# MCU.net
KiCad netlist of a schematic drawn in Altium Designer
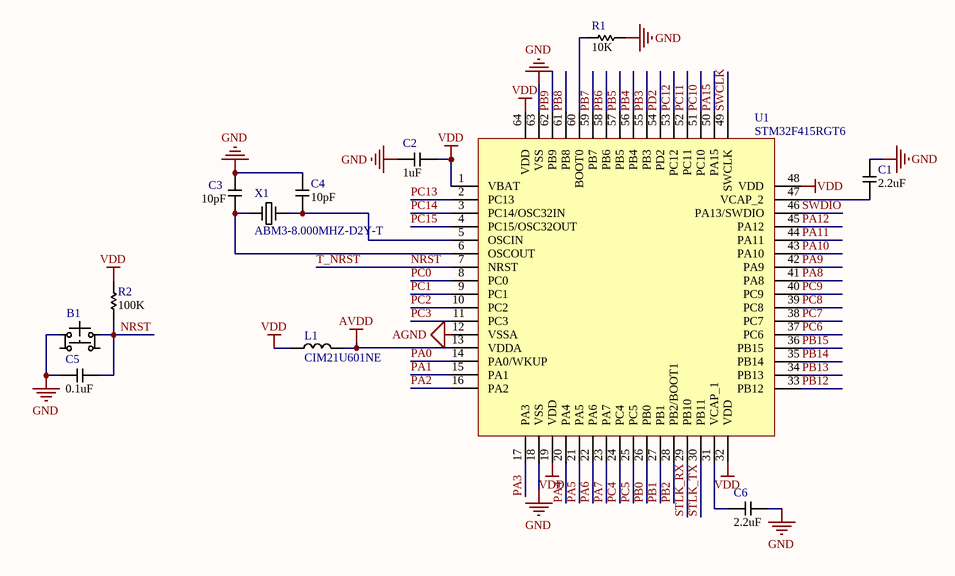
[diagram p0: MCU.SchDoc]

(export (version "E")
  (design (tool "Eeschema 10.0.6"))
  (components
    (comp (ref "B1")
      (value "DTSM-65R-V-T/R")
      (footprint "Diptronics_DTSM-65_Red_4")
      (description "Button_SMD_4_6x6x9.5_Diptronics")
      (fields (field (name "MANUFACTURER") "Diptronics"))
      (libsource (lib "Button") (part "DTSM-65R-V-T/R"))
    )
    (comp (ref "C1")
      (value "2.2uF")
      (footprint "Kemet_0805_X7R")
      (description "Cap_0805_0.1uF_25VDC_Kemet")
      (fields (field (name "MANUFACTURER") "Kemet") (field (name "VOLTAGE") "25VDC"))
      (libsource (lib "Capacitor") (part "C0805C104K3RACTU"))
    )
    (comp (ref "C2")
      (value "1uF")
      (footprint "Kemet_0805_X7R")
      (description "Cap_0805_1uF_16VDC_Kemet")
      (fields (field (name "MANUFACTURER") "Kemet") (field (name "VOLTAGE") "16VDC"))
      (libsource (lib "Capacitor") (part "C0805C105K4RACTU"))
    )
    (comp (ref "C3")
      (value "10pF")
      (footprint "Kemet_0805_X7R")
      (description "Cap_0805_0.1uF_25VDC_Kemet")
      (fields (field (name "MANUFACTURER") "Kemet") (field (name "VOLTAGE") "25VDC"))
      (libsource (lib "Capacitor") (part "C0805C104K3RACTU"))
    )
    (comp (ref "C4")
      (value "10pF")
      (footprint "Kemet_0805_X7R")
      (description "Cap_0805_0.1uF_25VDC_Kemet")
      (fields (field (name "MANUFACTURER") "Kemet") (field (name "VOLTAGE") "25VDC"))
      (libsource (lib "Capacitor") (part "C0805C104K3RACTU"))
    )
    (comp (ref "C5")
      (value "0.1uF")
      (footprint "Kemet_0805_X7R")
      (description "Cap_0805_0.1uF_25VDC_Kemet")
      (fields (field (name "MANUFACTURER") "Kemet") (field (name "VOLTAGE") "25VDC"))
      (libsource (lib "Capacitor") (part "C0805C104K3RACTU"))
    )
    (comp (ref "C6")
      (value "2.2uF")
      (footprint "Kemet_0805_X7R")
      (description "Cap_0805_0.1uF_25VDC_Kemet")
      (fields (field (name "MANUFACTURER") "Kemet") (field (name "VOLTAGE") "25VDC"))
      (libsource (lib "Capacitor") (part "C0805C104K3RACTU"))
    )
    (comp (ref "L1")
      (value "CIM21U601NE")
      (footprint "SAMSUNG_INDC200X125X110L45N")
      (description "Bead_600R_500mA_0805_Samsung")
      (fields (field (name "MANUFACTURER") "Samsung"))
      (libsource (lib "Inductor") (part "CIM21U601NE"))
    )
    (comp (ref "R1")
      (value "10K")
      (footprint "VISHAY_RESC205X125X50L35_30N")
      (description "Res_0805_0R_1/8W_Vishay")
      (fields (field (name "MANUFACTURER") "Vishay") (field (name "POWER") "1/8W"))
      (libsource (lib "Resistor") (part "CRCW08050000Z0EA"))
    )
    (comp (ref "R2")
      (value "100K")
      (footprint "VISHAY_RESC205X125X50L35_30N")
      (description "Res_0805_0R_1/8W_Vishay")
      (fields (field (name "MANUFACTURER") "Vishay") (field (name "POWER") "1/8W"))
      (libsource (lib "Resistor") (part "CRCW08050000Z0EA"))
    )
    (comp (ref "U1")
      (value "STM32F415RGT6")
      (footprint "STM_QFP64P50_1200X1200X160L60X22N")
      (description "Microcontroller_STM")
      (fields (field (name "MANUFACTURER") "STM"))
      (libsource (lib "Microcontroller") (part "STM32F415RGT6"))
    )
    (comp (ref "X1")
      (value "ABM3-8.000MHZ-D2Y-T")
      (footprint "ABRACON_XTALDFN2_500X320X130L130X200N")
      (description "Crystal_8MHz_18pF_140R_20PPM_30PPM_Abracon")
      (fields (field (name "MANUFACTURER") "Abracon"))
      (libsource (lib "Crystal") (part "ABM3-8.000MHZ-D2Y-T"))
    )
  )
  (nets
    (net (code "1") (name "/NRST") (class "Default")
      (node (ref "B1") (pin "3") (pinfunction "3_3") (pintype "passive"))
      (node (ref "C5") (pin "2") (pinfunction "2_2") (pintype "passive"))
      (node (ref "R2") (pin "2") (pinfunction "2_2") (pintype "passive"))
      (node (ref "U1") (pin "7") (pinfunction "NRST_7") (pintype "passive"))
    )
    (net (code "2") (name "/PA0") (class "Default")
      (node (ref "U1") (pin "14") (pinfunction "PA0/WKUP_14") (pintype "passive"))
    )
    (net (code "3") (name "/PA1") (class "Default")
      (node (ref "U1") (pin "15") (pinfunction "PA1_15") (pintype "passive"))
    )
    (net (code "4") (name "/PA2") (class "Default")
      (node (ref "U1") (pin "16") (pinfunction "PA2_16") (pintype "passive"))
    )
    (net (code "5") (name "/PA3") (class "Default")
      (node (ref "U1") (pin "17") (pinfunction "PA3_17") (pintype "passive"))
    )
    (net (code "6") (name "/PA4") (class "Default")
      (node (ref "U1") (pin "20") (pinfunction "PA4_20") (pintype "passive"))
    )
    (net (code "7") (name "/PA5") (class "Default")
      (node (ref "U1") (pin "21") (pinfunction "PA5_21") (pintype "passive"))
    )
    (net (code "8") (name "/PA6") (class "Default")
      (node (ref "U1") (pin "22") (pinfunction "PA6_22") (pintype "passive"))
    )
    (net (code "9") (name "/PA7") (class "Default")
      (node (ref "U1") (pin "23") (pinfunction "PA7_23") (pintype "passive"))
    )
    (net (code "10") (name "/PA8") (class "Default")
      (node (ref "U1") (pin "41") (pinfunction "PA8_41") (pintype "passive"))
    )
    (net (code "11") (name "/PA9") (class "Default")
      (node (ref "U1") (pin "42") (pinfunction "PA9_42") (pintype "passive"))
    )
    (net (code "12") (name "/PA10") (class "Default")
      (node (ref "U1") (pin "43") (pinfunction "PA10_43") (pintype "passive"))
    )
    (net (code "13") (name "/PA11") (class "Default")
      (node (ref "U1") (pin "44") (pinfunction "PA11_44") (pintype "passive"))
    )
    (net (code "14") (name "/PA12") (class "Default")
      (node (ref "U1") (pin "45") (pinfunction "PA12_45") (pintype "passive"))
    )
    (net (code "15") (name "/PA15") (class "Default")
      (node (ref "U1") (pin "50") (pinfunction "PA15_50") (pintype "passive"))
    )
    (net (code "16") (name "/PB0") (class "Default")
      (node (ref "U1") (pin "26") (pinfunction "PB0_26") (pintype "passive"))
    )
    (net (code "17") (name "/PB1") (class "Default")
      (node (ref "U1") (pin "27") (pinfunction "PB1_27") (pintype "passive"))
    )
    (net (code "18") (name "/PB2") (class "Default")
      (node (ref "U1") (pin "28") (pinfunction "PB2/BOOT1_28") (pintype "passive"))
    )
    (net (code "19") (name "/PB3") (class "Default")
      (node (ref "U1") (pin "55") (pinfunction "PB3_55") (pintype "passive"))
    )
    (net (code "20") (name "/PB4") (class "Default")
      (node (ref "U1") (pin "56") (pinfunction "PB4_56") (pintype "passive"))
    )
    (net (code "21") (name "/PB5") (class "Default")
      (node (ref "U1") (pin "57") (pinfunction "PB5_57") (pintype "passive"))
    )
    (net (code "22") (name "/PB6") (class "Default")
      (node (ref "U1") (pin "58") (pinfunction "PB6_58") (pintype "passive"))
    )
    (net (code "23") (name "/PB7") (class "Default")
      (node (ref "U1") (pin "59") (pinfunction "PB7_59") (pintype "passive"))
    )
    (net (code "24") (name "/PB8") (class "Default")
      (node (ref "U1") (pin "61") (pinfunction "PB8_61") (pintype "passive"))
    )
    (net (code "25") (name "/PB9") (class "Default")
      (node (ref "U1") (pin "62") (pinfunction "PB9_62") (pintype "passive"))
    )
    (net (code "26") (name "/PB12") (class "Default")
      (node (ref "U1") (pin "33") (pinfunction "PB12_33") (pintype "passive"))
    )
    (net (code "27") (name "/PB13") (class "Default")
      (node (ref "U1") (pin "34") (pinfunction "PB13_34") (pintype "passive"))
    )
    (net (code "28") (name "/PB14") (class "Default")
      (node (ref "U1") (pin "35") (pinfunction "PB14_35") (pintype "passive"))
    )
    (net (code "29") (name "/PB15") (class "Default")
      (node (ref "U1") (pin "36") (pinfunction "PB15_36") (pintype "passive"))
    )
    (net (code "30") (name "/PC0") (class "Default")
      (node (ref "U1") (pin "8") (pinfunction "PC0_8") (pintype "passive"))
    )
    (net (code "31") (name "/PC1") (class "Default")
      (node (ref "U1") (pin "9") (pinfunction "PC1_9") (pintype "passive"))
    )
    (net (code "32") (name "/PC2") (class "Default")
      (node (ref "U1") (pin "10") (pinfunction "PC2_10") (pintype "passive"))
    )
    (net (code "33") (name "/PC3") (class "Default")
      (node (ref "U1") (pin "11") (pinfunction "PC3_11") (pintype "passive"))
    )
    (net (code "34") (name "/PC4") (class "Default")
      (node (ref "U1") (pin "24") (pinfunction "PC4_24") (pintype "passive"))
    )
    (net (code "35") (name "/PC5") (class "Default")
      (node (ref "U1") (pin "25") (pinfunction "PC5_25") (pintype "passive"))
    )
    (net (code "36") (name "/PC6") (class "Default")
      (node (ref "U1") (pin "37") (pinfunction "PC6_37") (pintype "passive"))
    )
    (net (code "37") (name "/PC7") (class "Default")
      (node (ref "U1") (pin "38") (pinfunction "PC7_38") (pintype "passive"))
    )
    (net (code "38") (name "/PC8") (class "Default")
      (node (ref "U1") (pin "39") (pinfunction "PC8_39") (pintype "passive"))
    )
    (net (code "39") (name "/PC9") (class "Default")
      (node (ref "U1") (pin "40") (pinfunction "PC9_40") (pintype "passive"))
    )
    (net (code "40") (name "/PC10") (class "Default")
      (node (ref "U1") (pin "51") (pinfunction "PC10_51") (pintype "passive"))
    )
    (net (code "41") (name "/PC11") (class "Default")
      (node (ref "U1") (pin "52") (pinfunction "PC11_52") (pintype "passive"))
    )
    (net (code "42") (name "/PC12") (class "Default")
      (node (ref "U1") (pin "53") (pinfunction "PC12_53") (pintype "passive"))
    )
    (net (code "43") (name "/PC13") (class "Default")
      (node (ref "U1") (pin "2") (pinfunction "PC13_2") (pintype "passive"))
    )
    (net (code "44") (name "/PC14") (class "Default")
      (node (ref "U1") (pin "3") (pinfunction "PC14/OSC32IN_3") (pintype "passive"))
    )
    (net (code "45") (name "/PC15") (class "Default")
      (node (ref "U1") (pin "4") (pinfunction "PC15/OSC32OUT_4") (pintype "passive"))
    )
    (net (code "46") (name "/PD2") (class "Default")
      (node (ref "U1") (pin "54") (pinfunction "PD2_54") (pintype "passive"))
    )
    (net (code "47") (name "/STLK_RX") (class "Default")
      (node (ref "U1") (pin "29") (pinfunction "PB10_29") (pintype "passive"))
    )
    (net (code "48") (name "/STLK_TX") (class "Default")
      (node (ref "U1") (pin "30") (pinfunction "PB11_30") (pintype "passive"))
    )
    (net (code "49") (name "/SWCLK") (class "Default")
      (node (ref "U1") (pin "49") (pinfunction "SWCLK_49") (pintype "passive"))
    )
    (net (code "50") (name "/SWDIO") (class "Default")
      (node (ref "U1") (pin "46") (pinfunction "PA13/SWDIO_46") (pintype "passive"))
    )
    (net (code "51") (name "AGND") (class "Default")
      (node (ref "U1") (pin "12") (pinfunction "VSSA_12") (pintype "passive"))
    )
    (net (code "52") (name "AVDD") (class "Default")
      (node (ref "L1") (pin "2") (pinfunction "2_2") (pintype "passive"))
      (node (ref "U1") (pin "13") (pinfunction "VDDA_13") (pintype "passive"))
    )
    (net (code "53") (name "GND") (class "Default")
      (node (ref "B1") (pin "1") (pinfunction "1_1") (pintype "passive"))
      (node (ref "C1") (pin "1") (pinfunction "1_1") (pintype "passive"))
      (node (ref "C2") (pin "1") (pinfunction "1_1") (pintype "passive"))
      (node (ref "C3") (pin "2") (pinfunction "2_2") (pintype "passive"))
      (node (ref "C4") (pin "2") (pinfunction "2_2") (pintype "passive"))
      (node (ref "C5") (pin "1") (pinfunction "1_1") (pintype "passive"))
      (node (ref "C6") (pin "1") (pinfunction "1_1") (pintype "passive"))
      (node (ref "R1") (pin "1") (pinfunction "1_1") (pintype "passive"))
      (node (ref "U1") (pin "18") (pinfunction "VSS_18") (pintype "passive"))
      (node (ref "U1") (pin "63") (pinfunction "VSS_63") (pintype "passive"))
    )
    (net (code "54") (name "Net-(U1-BOOT0)") (class "Default")
      (node (ref "R1") (pin "2") (pinfunction "2_2") (pintype "passive"))
      (node (ref "U1") (pin "60") (pinfunction "BOOT0_60") (pintype "passive"))
    )
    (net (code "55") (name "Net-(U1-OSCIN)") (class "Default")
      (node (ref "C4") (pin "1") (pinfunction "1_1") (pintype "passive"))
      (node (ref "U1") (pin "5") (pinfunction "OSCIN_5") (pintype "passive"))
      (node (ref "X1") (pin "2") (pinfunction "2_2") (pintype "passive"))
    )
    (net (code "56") (name "Net-(U1-OSCOUT)") (class "Default")
      (node (ref "C3") (pin "1") (pinfunction "1_1") (pintype "passive"))
      (node (ref "U1") (pin "6") (pinfunction "OSCOUT_6") (pintype "passive"))
      (node (ref "X1") (pin "1") (pinfunction "1_1") (pintype "passive"))
    )
    (net (code "57") (name "Net-(U1-VCAP_1)") (class "Default")
      (node (ref "C6") (pin "2") (pinfunction "2_2") (pintype "passive"))
      (node (ref "U1") (pin "31") (pinfunction "VCAP_1_31") (pintype "passive"))
    )
    (net (code "58") (name "Net-(U1-VCAP_2)") (class "Default")
      (node (ref "C1") (pin "2") (pinfunction "2_2") (pintype "passive"))
      (node (ref "U1") (pin "47") (pinfunction "VCAP_2_47") (pintype "passive"))
    )
    (net (code "59") (name "VDD") (class "Default")
      (node (ref "C2") (pin "2") (pinfunction "2_2") (pintype "passive"))
      (node (ref "L1") (pin "1") (pinfunction "1_1") (pintype "passive"))
      (node (ref "R2") (pin "1") (pinfunction "1_1") (pintype "passive"))
      (node (ref "U1") (pin "1") (pinfunction "VBAT_1") (pintype "passive"))
      (node (ref "U1") (pin "19") (pinfunction "VDD_19") (pintype "passive"))
      (node (ref "U1") (pin "32") (pinfunction "VDD_32") (pintype "passive"))
      (node (ref "U1") (pin "48") (pinfunction "VDD_48") (pintype "passive"))
      (node (ref "U1") (pin "64") (pinfunction "VDD_64") (pintype "passive"))
    )
    (net (code "60") (name "unconnected-(B1-Pad2)") (class "Default")
      (node (ref "B1") (pin "2") (pinfunction "2_2") (pintype "passive"))
    )
    (net (code "61") (name "unconnected-(B1-Pad4)") (class "Default")
      (node (ref "B1") (pin "4") (pinfunction "4_4") (pintype "passive"))
    )
  )
)
